# driverboard-v1.net
KiCad netlist of a schematic drawn in EAGLE
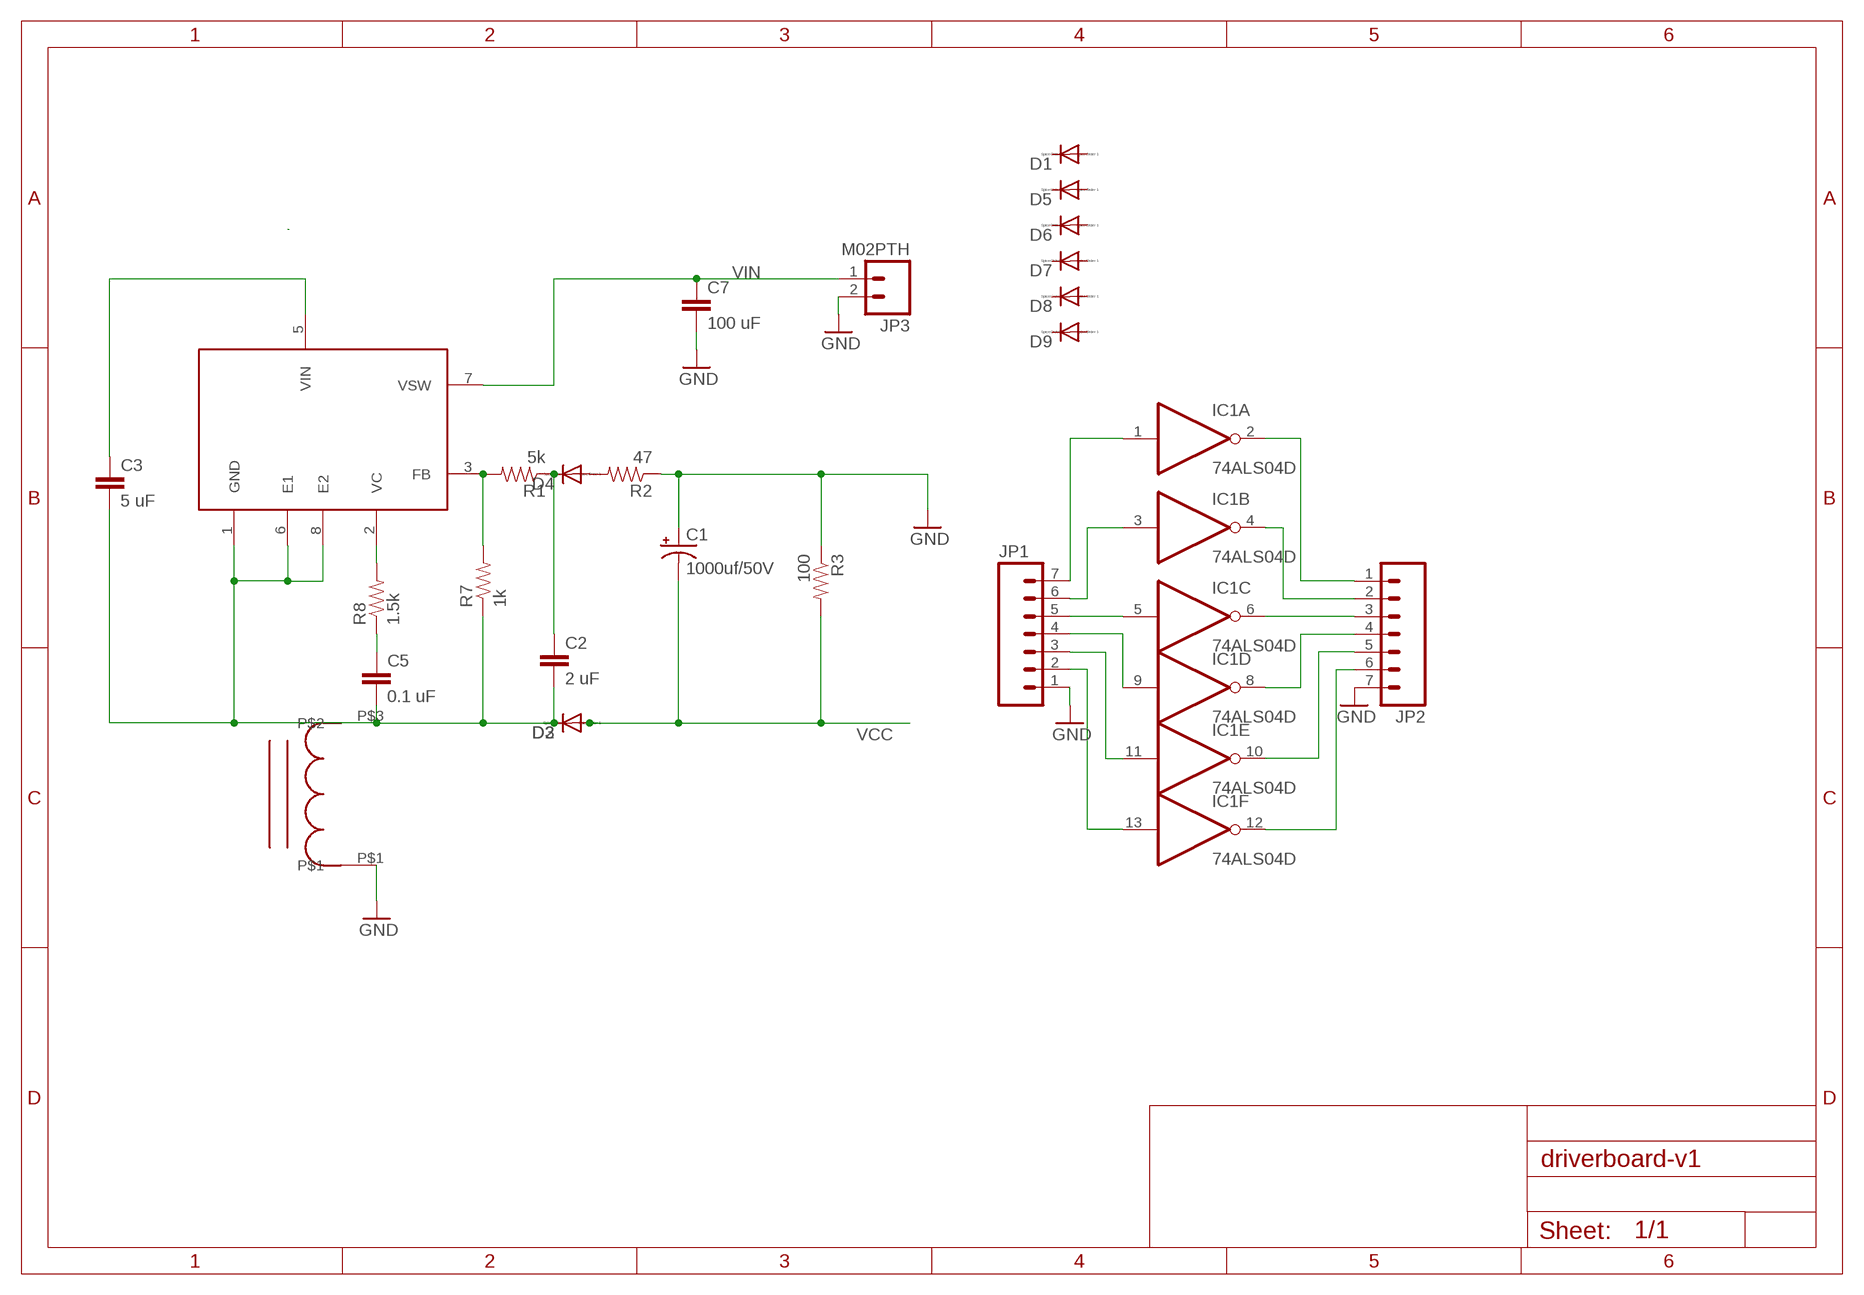
[diagram p0: schematic, sheet 1]

(export (version "E")
  (design (tool "Eeschema 10.0.6"))
  (components
    (comp (ref "C1")
      (value "1000uf/50V")
      (footprint "eagle-import:CPOL-RADIAL-1000UF-25V-KIT")
      (libsource (lib "eagle-import") (part "1000UF-25V(PTH)KIT"))
    )
    (comp (ref "C2")
      (value "2 uF")
      (footprint "eagle-import:0805")
      (libsource (lib "eagle-import") (part "CAP0805"))
    )
    (comp (ref "C3")
      (value "5 uF")
      (footprint "eagle-import:0805")
      (libsource (lib "eagle-import") (part "CAP0805"))
    )
    (comp (ref "C5")
      (value "0.1 uF")
      (footprint "eagle-import:0805")
      (libsource (lib "eagle-import") (part "CAP0805"))
    )
    (comp (ref "C7")
      (value "100 uF")
      (footprint "eagle-import:1206")
      (libsource (lib "eagle-import") (part "CAP1206"))
    )
    (comp (ref "D1")
      (value "DIODE-DO-214AC")
      (footprint "eagle-import:DO-214AC")
      (libsource (lib "eagle-import") (part "DIODE-DO-214AC"))
    )
    (comp (ref "D2")
      (value "DIODE-DO-214AC")
      (footprint "eagle-import:DO-214AC")
      (libsource (lib "eagle-import") (part "DIODE-DO-214AC"))
    )
    (comp (ref "D3")
      (value "DIODE-DO-214AC")
      (footprint "eagle-import:DO-214AC")
      (libsource (lib "eagle-import") (part "DIODE-DO-214AC"))
    )
    (comp (ref "D4")
      (value "DIODE-DO-214AC")
      (footprint "eagle-import:DO-214AC")
      (libsource (lib "eagle-import") (part "DIODE-DO-214AC"))
    )
    (comp (ref "D5")
      (value "DIODE-DO-214AC")
      (footprint "eagle-import:DO-214AC")
      (libsource (lib "eagle-import") (part "DIODE-DO-214AC"))
    )
    (comp (ref "D6")
      (value "DIODE-DO-214AC")
      (footprint "eagle-import:DO-214AC")
      (libsource (lib "eagle-import") (part "DIODE-DO-214AC"))
    )
    (comp (ref "D7")
      (value "DIODE-DO-214AC")
      (footprint "eagle-import:DO-214AC")
      (libsource (lib "eagle-import") (part "DIODE-DO-214AC"))
    )
    (comp (ref "D8")
      (value "DIODE-DO-214AC")
      (footprint "eagle-import:DO-214AC")
      (libsource (lib "eagle-import") (part "DIODE-DO-214AC"))
    )
    (comp (ref "D9")
      (value "DIODE-DO-214AC")
      (footprint "eagle-import:DO-214AC")
      (libsource (lib "eagle-import") (part "DIODE-DO-214AC"))
    )
    (comp (ref "IC1")
      (value "74ALS04D")
      (footprint "eagle-import:SO14")
      (libsource (lib "eagle-import") (part "7404DALS"))
    )
    (comp (ref "JP1")
      (value "M07")
      (footprint "eagle-import:1X07")
      (libsource (lib "eagle-import") (part "M07"))
    )
    (comp (ref "JP2")
      (value "M07")
      (footprint "eagle-import:1X07")
      (libsource (lib "eagle-import") (part "M07"))
    )
    (comp (ref "JP3")
      (value "M02PTH")
      (footprint "eagle-import:1X02")
      (libsource (lib "eagle-import") (part "M02PTH"))
    )
    (comp (ref "L2")
      (value "52626-L")
      (footprint "eagle-import:52626-L")
      (libsource (lib "eagle-import") (part "52626-L"))
    )
    (comp (ref "R1")
      (value "5k")
      (footprint "eagle-import:0603-RES")
      (libsource (lib "eagle-import") (part "RESISTOR0603"))
    )
    (comp (ref "R2")
      (value "47")
      (footprint "eagle-import:0603-RES")
      (libsource (lib "eagle-import") (part "RESISTOR0603"))
    )
    (comp (ref "R3")
      (value "100")
      (footprint "eagle-import:0603-RES")
      (libsource (lib "eagle-import") (part "RESISTOR0603"))
    )
    (comp (ref "R7")
      (value "1k")
      (footprint "eagle-import:0603-RES")
      (libsource (lib "eagle-import") (part "RESISTOR0603"))
    )
    (comp (ref "R8")
      (value "1.5k")
      (footprint "eagle-import:0603-RES")
      (libsource (lib "eagle-import") (part "RESISTOR0603"))
    )
    (comp (ref "U3")
      (value "1072-BOOST")
      (footprint "eagle-import:1072-BOOST")
      (libsource (lib "eagle-import") (part "1072-BOOST"))
    )
  )
  (nets
    (net (code "1") (name "/VCC") (class "Default")
      (node (ref "C1") (pin "-") (pinfunction "-_-") (pintype "passive"))
      (node (ref "D2") (pin "A") (pinfunction "A_A") (pintype "passive"))
      (node (ref "D3") (pin "A") (pinfunction "A_A") (pintype "passive"))
      (node (ref "R3") (pin "2") (pinfunction "2_2") (pintype "passive"))
    )
    (net (code "2") (name "/VIN") (class "Default")
      (node (ref "C7") (pin "1") (pinfunction "1_1") (pintype "passive"))
      (node (ref "JP3") (pin "1") (pinfunction "1_1") (pintype "passive"))
      (node (ref "U3") (pin "7") (pinfunction "VSW_7") (pintype "bidirectional"))
    )
    (net (code "3") (name "GND") (class "Default")
      (node (ref "C1") (pin "+") (pinfunction "+_+") (pintype "passive"))
      (node (ref "C7") (pin "2") (pinfunction "2_2") (pintype "passive"))
      (node (ref "JP1") (pin "1") (pinfunction "1_1") (pintype "passive"))
      (node (ref "JP2") (pin "7") (pinfunction "7_7") (pintype "passive"))
      (node (ref "JP3") (pin "2") (pinfunction "2_2") (pintype "passive"))
      (node (ref "L2") (pin "P$1") (pinfunction "P$1_P$1") (pintype "bidirectional"))
      (node (ref "R2") (pin "1") (pinfunction "1_1") (pintype "passive"))
      (node (ref "R3") (pin "1") (pinfunction "1_1") (pintype "passive"))
    )
    (net (code "4") (name "Net-(C2-Pad1)") (class "Default")
      (node (ref "C2") (pin "1") (pinfunction "1_1") (pintype "passive"))
      (node (ref "D4") (pin "C") (pinfunction "C_C") (pintype "passive"))
      (node (ref "R1") (pin "1") (pinfunction "1_1") (pintype "passive"))
    )
    (net (code "5") (name "Net-(C5-Pad1)") (class "Default")
      (node (ref "C5") (pin "1") (pinfunction "1_1") (pintype "passive"))
      (node (ref "R8") (pin "1") (pinfunction "1_1") (pintype "passive"))
    )
    (net (code "6") (name "Net-(D4-PadA)") (class "Default")
      (node (ref "D4") (pin "A") (pinfunction "A_A") (pintype "passive"))
      (node (ref "R2") (pin "2") (pinfunction "2_2") (pintype "passive"))
    )
    (net (code "7") (name "Net-(IC1A-I)") (class "Default")
      (node (ref "IC1") (pin "1") (pinfunction "I_1") (pintype "input"))
      (node (ref "JP1") (pin "7") (pinfunction "7_7") (pintype "passive"))
    )
    (net (code "8") (name "Net-(IC1A-O)") (class "Default")
      (node (ref "IC1") (pin "2") (pinfunction "O_2") (pintype "output"))
      (node (ref "JP2") (pin "1") (pinfunction "1_1") (pintype "passive"))
    )
    (net (code "9") (name "Net-(IC1B-I)") (class "Default")
      (node (ref "IC1") (pin "3") (pinfunction "I_3") (pintype "input"))
      (node (ref "JP1") (pin "6") (pinfunction "6_6") (pintype "passive"))
    )
    (net (code "10") (name "Net-(IC1B-O)") (class "Default")
      (node (ref "IC1") (pin "4") (pinfunction "O_4") (pintype "output"))
      (node (ref "JP2") (pin "2") (pinfunction "2_2") (pintype "passive"))
    )
    (net (code "11") (name "Net-(IC1C-I)") (class "Default")
      (node (ref "IC1") (pin "5") (pinfunction "I_5") (pintype "input"))
      (node (ref "JP1") (pin "5") (pinfunction "5_5") (pintype "passive"))
    )
    (net (code "12") (name "Net-(IC1C-O)") (class "Default")
      (node (ref "IC1") (pin "6") (pinfunction "O_6") (pintype "output"))
      (node (ref "JP2") (pin "3") (pinfunction "3_3") (pintype "passive"))
    )
    (net (code "13") (name "Net-(IC1D-I)") (class "Default")
      (node (ref "IC1") (pin "9") (pinfunction "I_9") (pintype "input"))
      (node (ref "JP1") (pin "4") (pinfunction "4_4") (pintype "passive"))
    )
    (net (code "14") (name "Net-(IC1D-O)") (class "Default")
      (node (ref "IC1") (pin "8") (pinfunction "O_8") (pintype "output"))
      (node (ref "JP2") (pin "4") (pinfunction "4_4") (pintype "passive"))
    )
    (net (code "15") (name "Net-(IC1E-I)") (class "Default")
      (node (ref "IC1") (pin "11") (pinfunction "I_11") (pintype "input"))
      (node (ref "JP1") (pin "3") (pinfunction "3_3") (pintype "passive"))
    )
    (net (code "16") (name "Net-(IC1E-O)") (class "Default")
      (node (ref "IC1") (pin "10") (pinfunction "O_10") (pintype "output"))
      (node (ref "JP2") (pin "5") (pinfunction "5_5") (pintype "passive"))
    )
    (net (code "17") (name "Net-(IC1F-I)") (class "Default")
      (node (ref "IC1") (pin "13") (pinfunction "I_13") (pintype "input"))
      (node (ref "JP1") (pin "2") (pinfunction "2_2") (pintype "passive"))
    )
    (net (code "18") (name "Net-(IC1F-O)") (class "Default")
      (node (ref "IC1") (pin "12") (pinfunction "O_12") (pintype "output"))
      (node (ref "JP2") (pin "6") (pinfunction "6_6") (pintype "passive"))
    )
    (net (code "19") (name "Net-(L2-P$2)") (class "Default")
      (node (ref "C2") (pin "2") (pinfunction "2_2") (pintype "passive"))
      (node (ref "C3") (pin "2") (pinfunction "2_2") (pintype "passive"))
      (node (ref "C5") (pin "2") (pinfunction "2_2") (pintype "passive"))
      (node (ref "D2") (pin "C") (pinfunction "C_C") (pintype "passive"))
      (node (ref "D3") (pin "C") (pinfunction "C_C") (pintype "passive"))
      (node (ref "L2") (pin "P$3") (pinfunction "P$2_P$3") (pintype "bidirectional"))
      (node (ref "R7") (pin "1") (pinfunction "1_1") (pintype "passive"))
      (node (ref "U3") (pin "1") (pinfunction "GND_1") (pintype "bidirectional"))
      (node (ref "U3") (pin "6") (pinfunction "E1_6") (pintype "bidirectional"))
      (node (ref "U3") (pin "8") (pinfunction "E2_8") (pintype "bidirectional"))
    )
    (net (code "20") (name "Net-(U3-FB)") (class "Default")
      (node (ref "R1") (pin "2") (pinfunction "2_2") (pintype "passive"))
      (node (ref "R7") (pin "2") (pinfunction "2_2") (pintype "passive"))
      (node (ref "U3") (pin "3") (pinfunction "FB_3") (pintype "bidirectional"))
    )
    (net (code "21") (name "Net-(U3-VC)") (class "Default")
      (node (ref "R8") (pin "2") (pinfunction "2_2") (pintype "passive"))
      (node (ref "U3") (pin "2") (pinfunction "VC_2") (pintype "bidirectional"))
    )
    (net (code "22") (name "Net-(U3-VIN)") (class "Default")
      (node (ref "C3") (pin "1") (pinfunction "1_1") (pintype "passive"))
      (node (ref "U3") (pin "5") (pinfunction "VIN_5") (pintype "bidirectional"))
    )
    (net (code "23") (name "unconnected-(D1-PadA)") (class "Default")
      (node (ref "D1") (pin "A") (pinfunction "A_A") (pintype "passive"))
    )
    (net (code "24") (name "unconnected-(D1-PadC)") (class "Default")
      (node (ref "D1") (pin "C") (pinfunction "C_C") (pintype "passive"))
    )
    (net (code "25") (name "unconnected-(D5-PadA)") (class "Default")
      (node (ref "D5") (pin "A") (pinfunction "A_A") (pintype "passive"))
    )
    (net (code "26") (name "unconnected-(D5-PadC)") (class "Default")
      (node (ref "D5") (pin "C") (pinfunction "C_C") (pintype "passive"))
    )
    (net (code "27") (name "unconnected-(D6-PadA)") (class "Default")
      (node (ref "D6") (pin "A") (pinfunction "A_A") (pintype "passive"))
    )
    (net (code "28") (name "unconnected-(D6-PadC)") (class "Default")
      (node (ref "D6") (pin "C") (pinfunction "C_C") (pintype "passive"))
    )
    (net (code "29") (name "unconnected-(D7-PadA)") (class "Default")
      (node (ref "D7") (pin "A") (pinfunction "A_A") (pintype "passive"))
    )
    (net (code "30") (name "unconnected-(D7-PadC)") (class "Default")
      (node (ref "D7") (pin "C") (pinfunction "C_C") (pintype "passive"))
    )
    (net (code "31") (name "unconnected-(D8-PadA)") (class "Default")
      (node (ref "D8") (pin "A") (pinfunction "A_A") (pintype "passive"))
    )
    (net (code "32") (name "unconnected-(D8-PadC)") (class "Default")
      (node (ref "D8") (pin "C") (pinfunction "C_C") (pintype "passive"))
    )
    (net (code "33") (name "unconnected-(D9-PadA)") (class "Default")
      (node (ref "D9") (pin "A") (pinfunction "A_A") (pintype "passive"))
    )
    (net (code "34") (name "unconnected-(D9-PadC)") (class "Default")
      (node (ref "D9") (pin "C") (pinfunction "C_C") (pintype "passive"))
    )
  )
)
